# usbftdi.net
KiCad netlist of a schematic drawn in EAGLE
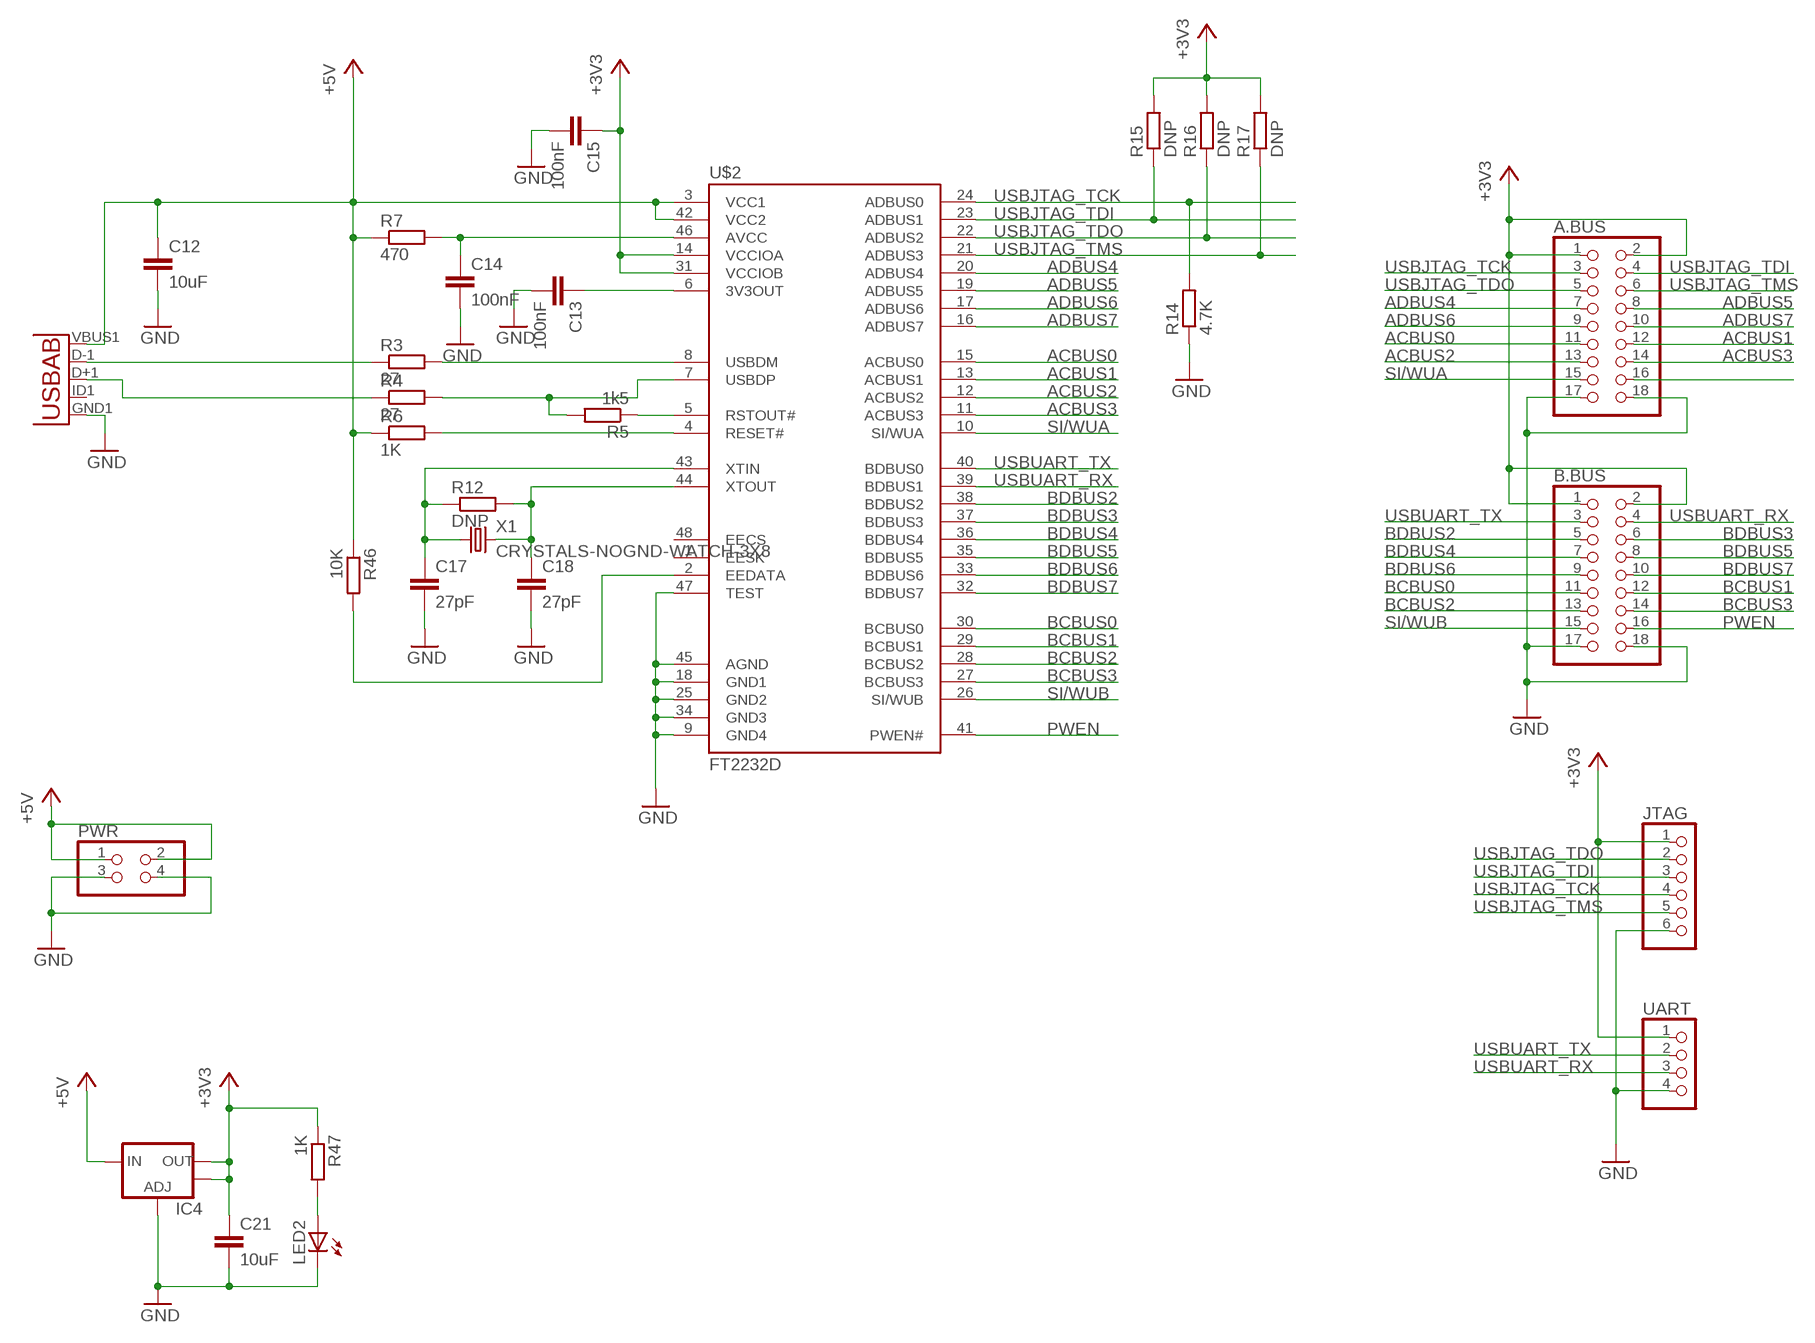
[diagram p0: schematic, sheet 1]

(export (version "E")
  (design (tool "Eeschema 10.0.6"))
  (components
    (comp (ref "A.BUS")
      (value "PINHD-2X9")
      (footprint "eagle-import:2X09")
      (libsource (lib "eagle-import") (part "PINHD-2X9"))
    )
    (comp (ref "B.BUS")
      (value "PINHD-2X9")
      (footprint "eagle-import:2X09")
      (libsource (lib "eagle-import") (part "PINHD-2X9"))
    )
    (comp (ref "C12")
      (value "10uF")
      (footprint "eagle-import:C0805")
      (libsource (lib "eagle-import") (part "C-EUC0805"))
    )
    (comp (ref "C13")
      (value "100nF")
      (footprint "eagle-import:C0603")
      (libsource (lib "eagle-import") (part "C-EUC0603"))
    )
    (comp (ref "C14")
      (value "100nF")
      (footprint "eagle-import:C0603")
      (libsource (lib "eagle-import") (part "C-EUC0603"))
    )
    (comp (ref "C15")
      (value "100nF")
      (footprint "eagle-import:C0603")
      (libsource (lib "eagle-import") (part "C-EUC0603"))
    )
    (comp (ref "C17")
      (value "27pF")
      (footprint "eagle-import:C0603")
      (libsource (lib "eagle-import") (part "C-EUC0603"))
    )
    (comp (ref "C18")
      (value "27pF")
      (footprint "eagle-import:C0603")
      (libsource (lib "eagle-import") (part "C-EUC0603"))
    )
    (comp (ref "C21")
      (value "10uF")
      (footprint "eagle-import:C0805")
      (libsource (lib "eagle-import") (part "C-EUC0805"))
    )
    (comp (ref "IC4")
      (value "V_REG_LM1117SOT223")
      (footprint "eagle-import:SOT223")
      (libsource (lib "eagle-import") (part "V_REG_LM1117SOT223"))
    )
    (comp (ref "JTAG")
      (value "PINHD-1X6")
      (footprint "eagle-import:1X06")
      (libsource (lib "eagle-import") (part "PINHD-1X6"))
    )
    (comp (ref "LED2")
      (value "LEDCHIPLED_0603")
      (footprint "eagle-import:CHIPLED_0603")
      (libsource (lib "eagle-import") (part "LEDCHIPLED_0603"))
    )
    (comp (ref "MICROUSB")
      (value "USB\"\"")
      (footprint "eagle-import:USB-MICRO-SMD")
      (libsource (lib "eagle-import") (part "USB{dblquote}{dblquote}"))
    )
    (comp (ref "PWR")
      (value "PINHD-2X2")
      (footprint "eagle-import:2X02")
      (libsource (lib "eagle-import") (part "PINHD-2X2"))
    )
    (comp (ref "R3")
      (value "27")
      (footprint "eagle-import:R0603")
      (libsource (lib "eagle-import") (part "R-EU_R0603"))
    )
    (comp (ref "R4")
      (value "27")
      (footprint "eagle-import:R0603")
      (libsource (lib "eagle-import") (part "R-EU_R0603"))
    )
    (comp (ref "R5")
      (value "1k5")
      (footprint "eagle-import:R0603")
      (libsource (lib "eagle-import") (part "R-EU_R0603"))
    )
    (comp (ref "R6")
      (value "1K")
      (footprint "eagle-import:R0603")
      (libsource (lib "eagle-import") (part "R-EU_R0603"))
    )
    (comp (ref "R7")
      (value "470")
      (footprint "eagle-import:R0603")
      (libsource (lib "eagle-import") (part "R-EU_R0603"))
    )
    (comp (ref "R12")
      (value "DNP")
      (footprint "eagle-import:R0603")
      (libsource (lib "eagle-import") (part "R-EU_R0603"))
    )
    (comp (ref "R14")
      (value "4.7K")
      (footprint "eagle-import:R0603")
      (libsource (lib "eagle-import") (part "R-EU_R0603"))
    )
    (comp (ref "R15")
      (value "DNP")
      (footprint "eagle-import:R0603")
      (libsource (lib "eagle-import") (part "R-EU_R0603"))
    )
    (comp (ref "R16")
      (value "DNP")
      (footprint "eagle-import:R0603")
      (libsource (lib "eagle-import") (part "R-EU_R0603"))
    )
    (comp (ref "R17")
      (value "DNP")
      (footprint "eagle-import:R0603")
      (libsource (lib "eagle-import") (part "R-EU_R0603"))
    )
    (comp (ref "R46")
      (value "10K")
      (footprint "eagle-import:R0603")
      (libsource (lib "eagle-import") (part "R-EU_R0603"))
    )
    (comp (ref "R47")
      (value "1K")
      (footprint "eagle-import:R0603")
      (libsource (lib "eagle-import") (part "R-EU_R0603"))
    )
    (comp (ref "U$2")
      (value "FT2232D")
      (footprint "eagle-import:LQFP-48")
      (libsource (lib "eagle-import") (part "FT2232D"))
    )
    (comp (ref "UART")
      (value "PINHD-1X4")
      (footprint "eagle-import:1X04")
      (libsource (lib "eagle-import") (part "PINHD-1X4"))
    )
    (comp (ref "X1")
      (value "CRYSTALS-NOGND-WATCH-3X8")
      (footprint "eagle-import:WATCH-3X8")
      (libsource (lib "eagle-import") (part "CRYSTALS-NOGND-WATCH-3X8"))
    )
  )
  (nets
    (net (code "1") (name "+3V3") (class "Default")
      (node (ref "A.BUS") (pin "1") (pinfunction "1_1") (pintype "passive"))
      (node (ref "A.BUS") (pin "2") (pinfunction "2_2") (pintype "passive"))
      (node (ref "B.BUS") (pin "1") (pinfunction "1_1") (pintype "passive"))
      (node (ref "B.BUS") (pin "2") (pinfunction "2_2") (pintype "passive"))
      (node (ref "C15") (pin "1") (pinfunction "1_1") (pintype "passive"))
      (node (ref "C21") (pin "1") (pinfunction "1_1") (pintype "passive"))
      (node (ref "IC4") (pin "2") (pinfunction "OUT_2") (pintype "output"))
      (node (ref "IC4") (pin "4") (pinfunction "OUT_4") (pintype "output"))
      (node (ref "JTAG") (pin "1") (pinfunction "1_1") (pintype "passive"))
      (node (ref "R15") (pin "2") (pinfunction "2_2") (pintype "passive"))
      (node (ref "R16") (pin "2") (pinfunction "2_2") (pintype "passive"))
      (node (ref "R17") (pin "2") (pinfunction "2_2") (pintype "passive"))
      (node (ref "R47") (pin "1") (pinfunction "1_1") (pintype "passive"))
      (node (ref "U$2") (pin "14") (pinfunction "VCCIOA_14") (pintype "power_in"))
      (node (ref "U$2") (pin "31") (pinfunction "VCCIOB_31") (pintype "bidirectional"))
      (node (ref "UART") (pin "1") (pinfunction "1_1") (pintype "passive"))
    )
    (net (code "2") (name "+5V") (class "Default")
      (node (ref "C12") (pin "1") (pinfunction "1_1") (pintype "passive"))
      (node (ref "IC4") (pin "3") (pinfunction "IN_3") (pintype "input"))
      (node (ref "MICROUSB") (pin "VBUS1") (pinfunction "VBUS_VBUS1") (pintype "bidirectional"))
      (node (ref "PWR") (pin "1") (pinfunction "1_1") (pintype "passive"))
      (node (ref "PWR") (pin "2") (pinfunction "2_2") (pintype "passive"))
      (node (ref "R46") (pin "1") (pinfunction "1_1") (pintype "passive"))
      (node (ref "R6") (pin "1") (pinfunction "1_1") (pintype "passive"))
      (node (ref "R7") (pin "1") (pinfunction "1_1") (pintype "passive"))
      (node (ref "U$2") (pin "3") (pinfunction "VCC1_3") (pintype "power_in"))
      (node (ref "U$2") (pin "42") (pinfunction "VCC2_42") (pintype "power_in"))
    )
    (net (code "3") (name "/ACBUS0") (class "Default")
      (node (ref "A.BUS") (pin "11") (pinfunction "11_11") (pintype "passive"))
      (node (ref "U$2") (pin "15") (pinfunction "ACBUS0_15") (pintype "bidirectional"))
    )
    (net (code "4") (name "/ACBUS1") (class "Default")
      (node (ref "A.BUS") (pin "12") (pinfunction "12_12") (pintype "passive"))
      (node (ref "U$2") (pin "13") (pinfunction "ACBUS1_13") (pintype "bidirectional"))
    )
    (net (code "5") (name "/ACBUS2") (class "Default")
      (node (ref "A.BUS") (pin "13") (pinfunction "13_13") (pintype "passive"))
      (node (ref "U$2") (pin "12") (pinfunction "ACBUS2_12") (pintype "bidirectional"))
    )
    (net (code "6") (name "/ACBUS3") (class "Default")
      (node (ref "A.BUS") (pin "14") (pinfunction "14_14") (pintype "passive"))
      (node (ref "U$2") (pin "11") (pinfunction "ACBUS3_11") (pintype "bidirectional"))
    )
    (net (code "7") (name "/ADBUS4") (class "Default")
      (node (ref "A.BUS") (pin "7") (pinfunction "7_7") (pintype "passive"))
      (node (ref "U$2") (pin "20") (pinfunction "ADBUS4_20") (pintype "bidirectional"))
    )
    (net (code "8") (name "/ADBUS5") (class "Default")
      (node (ref "A.BUS") (pin "8") (pinfunction "8_8") (pintype "passive"))
      (node (ref "U$2") (pin "19") (pinfunction "ADBUS5_19") (pintype "bidirectional"))
    )
    (net (code "9") (name "/ADBUS6") (class "Default")
      (node (ref "A.BUS") (pin "9") (pinfunction "9_9") (pintype "passive"))
      (node (ref "U$2") (pin "17") (pinfunction "ADBUS6_17") (pintype "bidirectional"))
    )
    (net (code "10") (name "/ADBUS7") (class "Default")
      (node (ref "A.BUS") (pin "10") (pinfunction "10_10") (pintype "passive"))
      (node (ref "U$2") (pin "16") (pinfunction "ADBUS7_16") (pintype "bidirectional"))
    )
    (net (code "11") (name "/BCBUS0") (class "Default")
      (node (ref "B.BUS") (pin "11") (pinfunction "11_11") (pintype "passive"))
      (node (ref "U$2") (pin "30") (pinfunction "BCBUS0_30") (pintype "bidirectional"))
    )
    (net (code "12") (name "/BCBUS1") (class "Default")
      (node (ref "B.BUS") (pin "12") (pinfunction "12_12") (pintype "passive"))
      (node (ref "U$2") (pin "29") (pinfunction "BCBUS1_29") (pintype "bidirectional"))
    )
    (net (code "13") (name "/BCBUS2") (class "Default")
      (node (ref "B.BUS") (pin "13") (pinfunction "13_13") (pintype "passive"))
      (node (ref "U$2") (pin "28") (pinfunction "BCBUS2_28") (pintype "bidirectional"))
    )
    (net (code "14") (name "/BCBUS3") (class "Default")
      (node (ref "B.BUS") (pin "14") (pinfunction "14_14") (pintype "passive"))
      (node (ref "U$2") (pin "27") (pinfunction "BCBUS3_27") (pintype "bidirectional"))
    )
    (net (code "15") (name "/BDBUS2") (class "Default")
      (node (ref "B.BUS") (pin "5") (pinfunction "5_5") (pintype "passive"))
      (node (ref "U$2") (pin "38") (pinfunction "BDBUS2_38") (pintype "output"))
    )
    (net (code "16") (name "/BDBUS3") (class "Default")
      (node (ref "B.BUS") (pin "6") (pinfunction "6_6") (pintype "passive"))
      (node (ref "U$2") (pin "37") (pinfunction "BDBUS3_37") (pintype "input"))
    )
    (net (code "17") (name "/BDBUS4") (class "Default")
      (node (ref "B.BUS") (pin "7") (pinfunction "7_7") (pintype "passive"))
      (node (ref "U$2") (pin "36") (pinfunction "BDBUS4_36") (pintype "output"))
    )
    (net (code "18") (name "/BDBUS5") (class "Default")
      (node (ref "B.BUS") (pin "8") (pinfunction "8_8") (pintype "passive"))
      (node (ref "U$2") (pin "35") (pinfunction "BDBUS5_35") (pintype "input"))
    )
    (net (code "19") (name "/BDBUS6") (class "Default")
      (node (ref "B.BUS") (pin "9") (pinfunction "9_9") (pintype "passive"))
      (node (ref "U$2") (pin "33") (pinfunction "BDBUS6_33") (pintype "input"))
    )
    (net (code "20") (name "/BDBUS7") (class "Default")
      (node (ref "B.BUS") (pin "10") (pinfunction "10_10") (pintype "passive"))
      (node (ref "U$2") (pin "32") (pinfunction "BDBUS7_32") (pintype "input"))
    )
    (net (code "21") (name "/PWEN") (class "Default")
      (node (ref "B.BUS") (pin "16") (pinfunction "16_16") (pintype "passive"))
      (node (ref "U$2") (pin "41") (pinfunction "PWEN#_41") (pintype "bidirectional"))
    )
    (net (code "22") (name "/SI{slash}WUA") (class "Default")
      (node (ref "A.BUS") (pin "15") (pinfunction "15_15") (pintype "passive"))
      (node (ref "U$2") (pin "10") (pinfunction "SI/WUA_10") (pintype "bidirectional"))
    )
    (net (code "23") (name "/SI{slash}WUB") (class "Default")
      (node (ref "B.BUS") (pin "15") (pinfunction "15_15") (pintype "passive"))
      (node (ref "U$2") (pin "26") (pinfunction "SI/WUB_26") (pintype "bidirectional"))
    )
    (net (code "24") (name "/USBJTAG_TCK") (class "Default")
      (node (ref "A.BUS") (pin "3") (pinfunction "3_3") (pintype "passive"))
      (node (ref "JTAG") (pin "4") (pinfunction "4_4") (pintype "passive"))
      (node (ref "R14") (pin "2") (pinfunction "2_2") (pintype "passive"))
      (node (ref "U$2") (pin "24") (pinfunction "ADBUS0_24") (pintype "bidirectional"))
    )
    (net (code "25") (name "/USBJTAG_TDI") (class "Default")
      (node (ref "A.BUS") (pin "4") (pinfunction "4_4") (pintype "passive"))
      (node (ref "JTAG") (pin "3") (pinfunction "3_3") (pintype "passive"))
      (node (ref "R15") (pin "1") (pinfunction "1_1") (pintype "passive"))
      (node (ref "U$2") (pin "23") (pinfunction "ADBUS1_23") (pintype "bidirectional"))
    )
    (net (code "26") (name "/USBJTAG_TDO") (class "Default")
      (node (ref "A.BUS") (pin "5") (pinfunction "5_5") (pintype "passive"))
      (node (ref "JTAG") (pin "2") (pinfunction "2_2") (pintype "passive"))
      (node (ref "R16") (pin "1") (pinfunction "1_1") (pintype "passive"))
      (node (ref "U$2") (pin "22") (pinfunction "ADBUS2_22") (pintype "bidirectional"))
    )
    (net (code "27") (name "/USBJTAG_TMS") (class "Default")
      (node (ref "A.BUS") (pin "6") (pinfunction "6_6") (pintype "passive"))
      (node (ref "JTAG") (pin "5") (pinfunction "5_5") (pintype "passive"))
      (node (ref "R17") (pin "1") (pinfunction "1_1") (pintype "passive"))
      (node (ref "U$2") (pin "21") (pinfunction "ADBUS3_21") (pintype "bidirectional"))
    )
    (net (code "28") (name "/USBUART_RX") (class "Default")
      (node (ref "B.BUS") (pin "4") (pinfunction "4_4") (pintype "passive"))
      (node (ref "U$2") (pin "39") (pinfunction "BDBUS1_39") (pintype "input"))
      (node (ref "UART") (pin "3") (pinfunction "3_3") (pintype "passive"))
    )
    (net (code "29") (name "/USBUART_TX") (class "Default")
      (node (ref "B.BUS") (pin "3") (pinfunction "3_3") (pintype "passive"))
      (node (ref "U$2") (pin "40") (pinfunction "BDBUS0_40") (pintype "output"))
      (node (ref "UART") (pin "2") (pinfunction "2_2") (pintype "passive"))
    )
    (net (code "30") (name "GND") (class "Default")
      (node (ref "A.BUS") (pin "17") (pinfunction "17_17") (pintype "passive"))
      (node (ref "A.BUS") (pin "18") (pinfunction "18_18") (pintype "passive"))
      (node (ref "B.BUS") (pin "17") (pinfunction "17_17") (pintype "passive"))
      (node (ref "B.BUS") (pin "18") (pinfunction "18_18") (pintype "passive"))
      (node (ref "C12") (pin "2") (pinfunction "2_2") (pintype "passive"))
      (node (ref "C13") (pin "2") (pinfunction "2_2") (pintype "passive"))
      (node (ref "C14") (pin "2") (pinfunction "2_2") (pintype "passive"))
      (node (ref "C15") (pin "2") (pinfunction "2_2") (pintype "passive"))
      (node (ref "C17") (pin "2") (pinfunction "2_2") (pintype "passive"))
      (node (ref "C18") (pin "2") (pinfunction "2_2") (pintype "passive"))
      (node (ref "C21") (pin "2") (pinfunction "2_2") (pintype "passive"))
      (node (ref "IC4") (pin "1") (pinfunction "ADJ_1") (pintype "input"))
      (node (ref "JTAG") (pin "6") (pinfunction "6_6") (pintype "passive"))
      (node (ref "LED2") (pin "C") (pinfunction "C_C") (pintype "passive"))
      (node (ref "MICROUSB") (pin "GND1") (pinfunction "GND_GND1") (pintype "bidirectional"))
      (node (ref "PWR") (pin "3") (pinfunction "3_3") (pintype "passive"))
      (node (ref "PWR") (pin "4") (pinfunction "4_4") (pintype "passive"))
      (node (ref "R14") (pin "1") (pinfunction "1_1") (pintype "passive"))
      (node (ref "U$2") (pin "18") (pinfunction "GND1_18") (pintype "power_in"))
      (node (ref "U$2") (pin "25") (pinfunction "GND2_25") (pintype "power_in"))
      (node (ref "U$2") (pin "34") (pinfunction "GND3_34") (pintype "power_in"))
      (node (ref "U$2") (pin "45") (pinfunction "AGND_45") (pintype "power_in"))
      (node (ref "U$2") (pin "47") (pinfunction "TEST_47") (pintype "input"))
      (node (ref "U$2") (pin "9") (pinfunction "GND4_9") (pintype "bidirectional"))
      (node (ref "UART") (pin "4") (pinfunction "4_4") (pintype "passive"))
    )
    (net (code "31") (name "Net-(LED2-PadA)") (class "Default")
      (node (ref "LED2") (pin "A") (pinfunction "A_A") (pintype "passive"))
      (node (ref "R47") (pin "2") (pinfunction "2_2") (pintype "passive"))
    )
    (net (code "32") (name "Net-(MICROUSB-D+)") (class "Default")
      (node (ref "MICROUSB") (pin "D+1") (pinfunction "D+_D+1") (pintype "bidirectional"))
      (node (ref "R4") (pin "1") (pinfunction "1_1") (pintype "passive"))
    )
    (net (code "33") (name "Net-(MICROUSB-D-)") (class "Default")
      (node (ref "MICROUSB") (pin "D-1") (pinfunction "D-_D-1") (pintype "bidirectional"))
      (node (ref "R3") (pin "1") (pinfunction "1_1") (pintype "passive"))
    )
    (net (code "34") (name "Net-(U$2-3V3OUT)") (class "Default")
      (node (ref "C13") (pin "1") (pinfunction "1_1") (pintype "passive"))
      (node (ref "U$2") (pin "6") (pinfunction "3V3OUT_6") (pintype "output"))
    )
    (net (code "35") (name "Net-(U$2-AVCC)") (class "Default")
      (node (ref "C14") (pin "1") (pinfunction "1_1") (pintype "passive"))
      (node (ref "R7") (pin "2") (pinfunction "2_2") (pintype "passive"))
      (node (ref "U$2") (pin "46") (pinfunction "AVCC_46") (pintype "bidirectional"))
    )
    (net (code "36") (name "Net-(U$2-EEDATA)") (class "Default")
      (node (ref "R46") (pin "2") (pinfunction "2_2") (pintype "passive"))
      (node (ref "U$2") (pin "2") (pinfunction "EEDATA_2") (pintype "bidirectional"))
    )
    (net (code "37") (name "Net-(U$2-RESET#)") (class "Default")
      (node (ref "R6") (pin "2") (pinfunction "2_2") (pintype "passive"))
      (node (ref "U$2") (pin "4") (pinfunction "RESET#_4") (pintype "bidirectional"))
    )
    (net (code "38") (name "Net-(U$2-RSTOUT#)") (class "Default")
      (node (ref "R5") (pin "1") (pinfunction "1_1") (pintype "passive"))
      (node (ref "U$2") (pin "5") (pinfunction "RSTOUT#_5") (pintype "bidirectional"))
    )
    (net (code "39") (name "Net-(U$2-USBDM)") (class "Default")
      (node (ref "R3") (pin "2") (pinfunction "2_2") (pintype "passive"))
      (node (ref "U$2") (pin "8") (pinfunction "USBDM_8") (pintype "bidirectional"))
    )
    (net (code "40") (name "Net-(U$2-USBDP)") (class "Default")
      (node (ref "R4") (pin "2") (pinfunction "2_2") (pintype "passive"))
      (node (ref "R5") (pin "2") (pinfunction "2_2") (pintype "passive"))
      (node (ref "U$2") (pin "7") (pinfunction "USBDP_7") (pintype "bidirectional"))
    )
    (net (code "41") (name "Net-(U$2-XTIN)") (class "Default")
      (node (ref "C17") (pin "1") (pinfunction "1_1") (pintype "passive"))
      (node (ref "R12") (pin "1") (pinfunction "1_1") (pintype "passive"))
      (node (ref "U$2") (pin "43") (pinfunction "XTIN_43") (pintype "bidirectional"))
      (node (ref "X1") (pin "1") (pinfunction "1_1") (pintype "passive"))
    )
    (net (code "42") (name "Net-(U$2-XTOUT)") (class "Default")
      (node (ref "C18") (pin "1") (pinfunction "1_1") (pintype "passive"))
      (node (ref "R12") (pin "2") (pinfunction "2_2") (pintype "passive"))
      (node (ref "U$2") (pin "44") (pinfunction "XTOUT_44") (pintype "bidirectional"))
      (node (ref "X1") (pin "2") (pinfunction "2_2") (pintype "passive"))
    )
    (net (code "43") (name "unconnected-(A.BUS-Pad16)") (class "Default")
      (node (ref "A.BUS") (pin "16") (pinfunction "16_16") (pintype "passive"))
    )
    (net (code "44") (name "unconnected-(MICROUSB-USBID-PadID1)") (class "Default")
      (node (ref "MICROUSB") (pin "ID1") (pinfunction "USBID_ID1") (pintype "bidirectional"))
    )
    (net (code "45") (name "unconnected-(U$2-EECS-Pad48)") (class "Default")
      (node (ref "U$2") (pin "48") (pinfunction "EECS_48") (pintype "bidirectional"))
    )
    (net (code "46") (name "unconnected-(U$2-EESK-Pad1)") (class "Default")
      (node (ref "U$2") (pin "1") (pinfunction "EESK_1") (pintype "bidirectional"))
    )
  )
)
